# Tubes_1-3.net
KiCad netlist of a schematic drawn in Altium Designer
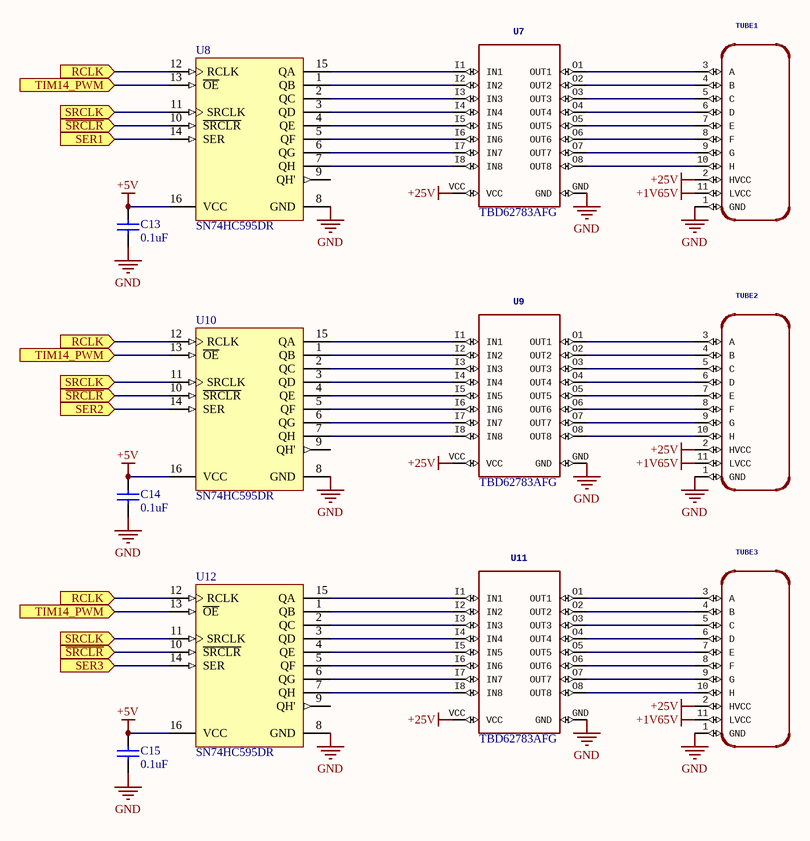
[diagram p0: Tubes 1-3.SchDoc]

(export (version "E")
  (design (tool "Eeschema 10.0.6"))
  (components
    (comp (ref "C13")
      (value "0.1uF")
      (footprint "CAPC1608X90X40ML10T20")
      (fields (field (name "TOLERANCE") "±10%") (field (name "MANUFACTURER") "Yageo"))
      (libsource (lib "Altium Content Vault") (part "CAP-NP-2"))
    )
    (comp (ref "C14")
      (value "0.1uF")
      (footprint "CAPC1608X90X40ML10T20")
      (fields (field (name "TOLERANCE") "±10%") (field (name "MANUFACTURER") "Yageo"))
      (libsource (lib "Altium Content Vault") (part "CAP-NP-2"))
    )
    (comp (ref "C15")
      (value "0.1uF")
      (footprint "CAPC1608X90X40ML10T20")
      (fields (field (name "TOLERANCE") "±10%") (field (name "MANUFACTURER") "Yageo"))
      (libsource (lib "Altium Content Vault") (part "CAP-NP-2"))
    )
    (comp (ref "TUBE1")
      (value "VFD-IV-11")
      (footprint "VFD-IV11")
      (libsource (lib "VFD-Clock") (part "VFD-IV-11"))
    )
    (comp (ref "TUBE2")
      (value "VFD-IV-11")
      (footprint "VFD-IV11")
      (libsource (lib "VFD-Clock") (part "VFD-IV-11"))
    )
    (comp (ref "TUBE3")
      (value "VFD-IV-11")
      (footprint "VFD-IV11")
      (libsource (lib "VFD-Clock") (part "VFD-IV-11"))
    )
    (comp (ref "U7")
      (value "TBD62783AFG")
      (footprint "TBD62783AFG")
      (description "TUBE1")
      (libsource (lib "TBD62783AFG") (part "TBD62783AFG"))
    )
    (comp (ref "U8")
      (value "SN74HC595DR")
      (footprint "D0016A_N")
      (description "8-Bit Shift Registers With 3-State Output Registers, D0016A, LARGE T&R")
      (fields
        (field (name "GENERIC PART NUMBER") "SN74HC595")
        (field (name "MANUFACTURER") "Texas Instruments")
      )
      (libsource (lib "VFD_Clock_lib") (part "CMP-0780-00037-3"))
    )
    (comp (ref "U9")
      (value "TBD62783AFG")
      (footprint "TBD62783AFG")
      (description "TUBE2")
      (libsource (lib "TBD62783AFG") (part "TBD62783AFG"))
    )
    (comp (ref "U10")
      (value "SN74HC595DR")
      (footprint "D0016A_N")
      (description "8-Bit Shift Registers With 3-State Output Registers, D0016A, LARGE T&R")
      (fields
        (field (name "GENERIC PART NUMBER") "SN74HC595")
        (field (name "MANUFACTURER") "Texas Instruments")
      )
      (libsource (lib "VFD_Clock_lib") (part "CMP-0780-00037-3"))
    )
    (comp (ref "U11")
      (value "TBD62783AFG")
      (footprint "TBD62783AFG")
      (description "TUBE3")
      (libsource (lib "TBD62783AFG") (part "TBD62783AFG"))
    )
    (comp (ref "U12")
      (value "SN74HC595DR")
      (footprint "D0016A_N")
      (description "8-Bit Shift Registers With 3-State Output Registers, D0016A, LARGE T&R")
      (fields
        (field (name "GENERIC PART NUMBER") "SN74HC595")
        (field (name "MANUFACTURER") "Texas Instruments")
      )
      (libsource (lib "VFD_Clock_lib") (part "CMP-0780-00037-3"))
    )
  )
  (nets
    (net (code "1") (name "+1V65V") (class "Default")
      (node (ref "TUBE1") (pin "11") (pinfunction "LVCC_11") (pintype "bidirectional"))
      (node (ref "TUBE2") (pin "11") (pinfunction "LVCC_11") (pintype "bidirectional"))
      (node (ref "TUBE3") (pin "11") (pinfunction "LVCC_11") (pintype "bidirectional"))
    )
    (net (code "2") (name "+5V") (class "Default")
      (node (ref "C13") (pin "2") (pinfunction "2_2") (pintype "passive"))
      (node (ref "C14") (pin "2") (pinfunction "2_2") (pintype "passive"))
      (node (ref "C15") (pin "2") (pinfunction "2_2") (pintype "passive"))
      (node (ref "U10") (pin "16") (pinfunction "VCC_16") (pintype "power_in"))
      (node (ref "U12") (pin "16") (pinfunction "VCC_16") (pintype "power_in"))
      (node (ref "U8") (pin "16") (pinfunction "VCC_16") (pintype "power_in"))
    )
    (net (code "3") (name "+25V") (class "Default")
      (node (ref "TUBE1") (pin "2") (pinfunction "HVCC_2") (pintype "bidirectional"))
      (node (ref "TUBE2") (pin "2") (pinfunction "HVCC_2") (pintype "bidirectional"))
      (node (ref "TUBE3") (pin "2") (pinfunction "HVCC_2") (pintype "bidirectional"))
      (node (ref "U11") (pin "VCC") (pinfunction "VCC_VCC") (pintype "bidirectional"))
      (node (ref "U7") (pin "VCC") (pinfunction "VCC_VCC") (pintype "bidirectional"))
      (node (ref "U9") (pin "VCC") (pinfunction "VCC_VCC") (pintype "bidirectional"))
    )
    (net (code "4") (name "/RCLK") (class "Default")
      (node (ref "U10") (pin "12") (pinfunction "RCLK_12") (pintype "input"))
      (node (ref "U12") (pin "12") (pinfunction "RCLK_12") (pintype "input"))
      (node (ref "U8") (pin "12") (pinfunction "RCLK_12") (pintype "input"))
    )
    (net (code "5") (name "/SER1") (class "Default")
      (node (ref "U8") (pin "14") (pinfunction "SER_14") (pintype "input"))
    )
    (net (code "6") (name "/SER2") (class "Default")
      (node (ref "U10") (pin "14") (pinfunction "SER_14") (pintype "input"))
    )
    (net (code "7") (name "/SER3") (class "Default")
      (node (ref "U12") (pin "14") (pinfunction "SER_14") (pintype "input"))
    )
    (net (code "8") (name "/SRCLK") (class "Default")
      (node (ref "U10") (pin "11") (pinfunction "SRCLK_11") (pintype "input"))
      (node (ref "U12") (pin "11") (pinfunction "SRCLK_11") (pintype "input"))
      (node (ref "U8") (pin "11") (pinfunction "SRCLK_11") (pintype "input"))
    )
    (net (code "9") (name "/SRCLR") (class "Default")
      (node (ref "U10") (pin "10") (pinfunction "~{SRCLR}_10") (pintype "input"))
      (node (ref "U12") (pin "10") (pinfunction "~{SRCLR}_10") (pintype "input"))
      (node (ref "U8") (pin "10") (pinfunction "~{SRCLR}_10") (pintype "input"))
    )
    (net (code "10") (name "/TIM14_PWM") (class "Default")
      (node (ref "U10") (pin "13") (pinfunction "~{OE}_13") (pintype "input"))
      (node (ref "U12") (pin "13") (pinfunction "~{OE}_13") (pintype "input"))
      (node (ref "U8") (pin "13") (pinfunction "~{OE}_13") (pintype "input"))
    )
    (net (code "11") (name "GND") (class "Default")
      (node (ref "C13") (pin "1") (pinfunction "1_1") (pintype "passive"))
      (node (ref "C14") (pin "1") (pinfunction "1_1") (pintype "passive"))
      (node (ref "C15") (pin "1") (pinfunction "1_1") (pintype "passive"))
      (node (ref "TUBE1") (pin "1") (pinfunction "GND_1") (pintype "bidirectional"))
      (node (ref "TUBE2") (pin "1") (pinfunction "GND_1") (pintype "bidirectional"))
      (node (ref "TUBE3") (pin "1") (pinfunction "GND_1") (pintype "bidirectional"))
      (node (ref "U10") (pin "8") (pinfunction "GND_8") (pintype "power_in"))
      (node (ref "U11") (pin "GND") (pinfunction "GND_GND") (pintype "bidirectional"))
      (node (ref "U12") (pin "8") (pinfunction "GND_8") (pintype "power_in"))
      (node (ref "U7") (pin "GND") (pinfunction "GND_GND") (pintype "bidirectional"))
      (node (ref "U8") (pin "8") (pinfunction "GND_8") (pintype "power_in"))
      (node (ref "U9") (pin "GND") (pinfunction "GND_GND") (pintype "bidirectional"))
    )
    (net (code "12") (name "Net-(TUBE1-A)") (class "Default")
      (node (ref "TUBE1") (pin "3") (pinfunction "A_3") (pintype "bidirectional"))
      (node (ref "U7") (pin "O1") (pinfunction "OUT1_O1") (pintype "bidirectional"))
    )
    (net (code "13") (name "Net-(TUBE1-B)") (class "Default")
      (node (ref "TUBE1") (pin "4") (pinfunction "B_4") (pintype "bidirectional"))
      (node (ref "U7") (pin "O2") (pinfunction "OUT2_O2") (pintype "bidirectional"))
    )
    (net (code "14") (name "Net-(TUBE1-C)") (class "Default")
      (node (ref "TUBE1") (pin "5") (pinfunction "C_5") (pintype "bidirectional"))
      (node (ref "U7") (pin "O3") (pinfunction "OUT3_O3") (pintype "bidirectional"))
    )
    (net (code "15") (name "Net-(TUBE1-D)") (class "Default")
      (node (ref "TUBE1") (pin "6") (pinfunction "D_6") (pintype "bidirectional"))
      (node (ref "U7") (pin "O4") (pinfunction "OUT4_O4") (pintype "bidirectional"))
    )
    (net (code "16") (name "Net-(TUBE1-E)") (class "Default")
      (node (ref "TUBE1") (pin "7") (pinfunction "E_7") (pintype "bidirectional"))
      (node (ref "U7") (pin "O5") (pinfunction "OUT5_O5") (pintype "bidirectional"))
    )
    (net (code "17") (name "Net-(TUBE1-F)") (class "Default")
      (node (ref "TUBE1") (pin "8") (pinfunction "F_8") (pintype "bidirectional"))
      (node (ref "U7") (pin "O6") (pinfunction "OUT6_O6") (pintype "bidirectional"))
    )
    (net (code "18") (name "Net-(TUBE1-G)") (class "Default")
      (node (ref "TUBE1") (pin "9") (pinfunction "G_9") (pintype "bidirectional"))
      (node (ref "U7") (pin "O7") (pinfunction "OUT7_O7") (pintype "bidirectional"))
    )
    (net (code "19") (name "Net-(TUBE1-H)") (class "Default")
      (node (ref "TUBE1") (pin "10") (pinfunction "H_10") (pintype "bidirectional"))
      (node (ref "U7") (pin "O8") (pinfunction "OUT8_O8") (pintype "bidirectional"))
    )
    (net (code "20") (name "Net-(TUBE2-A)") (class "Default")
      (node (ref "TUBE2") (pin "3") (pinfunction "A_3") (pintype "bidirectional"))
      (node (ref "U9") (pin "O1") (pinfunction "OUT1_O1") (pintype "bidirectional"))
    )
    (net (code "21") (name "Net-(TUBE2-B)") (class "Default")
      (node (ref "TUBE2") (pin "4") (pinfunction "B_4") (pintype "bidirectional"))
      (node (ref "U9") (pin "O2") (pinfunction "OUT2_O2") (pintype "bidirectional"))
    )
    (net (code "22") (name "Net-(TUBE2-C)") (class "Default")
      (node (ref "TUBE2") (pin "5") (pinfunction "C_5") (pintype "bidirectional"))
      (node (ref "U9") (pin "O3") (pinfunction "OUT3_O3") (pintype "bidirectional"))
    )
    (net (code "23") (name "Net-(TUBE2-D)") (class "Default")
      (node (ref "TUBE2") (pin "6") (pinfunction "D_6") (pintype "bidirectional"))
      (node (ref "U9") (pin "O4") (pinfunction "OUT4_O4") (pintype "bidirectional"))
    )
    (net (code "24") (name "Net-(TUBE2-E)") (class "Default")
      (node (ref "TUBE2") (pin "7") (pinfunction "E_7") (pintype "bidirectional"))
      (node (ref "U9") (pin "O5") (pinfunction "OUT5_O5") (pintype "bidirectional"))
    )
    (net (code "25") (name "Net-(TUBE2-F)") (class "Default")
      (node (ref "TUBE2") (pin "8") (pinfunction "F_8") (pintype "bidirectional"))
      (node (ref "U9") (pin "O6") (pinfunction "OUT6_O6") (pintype "bidirectional"))
    )
    (net (code "26") (name "Net-(TUBE2-G)") (class "Default")
      (node (ref "TUBE2") (pin "9") (pinfunction "G_9") (pintype "bidirectional"))
      (node (ref "U9") (pin "O7") (pinfunction "OUT7_O7") (pintype "bidirectional"))
    )
    (net (code "27") (name "Net-(TUBE2-H)") (class "Default")
      (node (ref "TUBE2") (pin "10") (pinfunction "H_10") (pintype "bidirectional"))
      (node (ref "U9") (pin "O8") (pinfunction "OUT8_O8") (pintype "bidirectional"))
    )
    (net (code "28") (name "Net-(TUBE3-A)") (class "Default")
      (node (ref "TUBE3") (pin "3") (pinfunction "A_3") (pintype "bidirectional"))
      (node (ref "U11") (pin "O1") (pinfunction "OUT1_O1") (pintype "bidirectional"))
    )
    (net (code "29") (name "Net-(TUBE3-B)") (class "Default")
      (node (ref "TUBE3") (pin "4") (pinfunction "B_4") (pintype "bidirectional"))
      (node (ref "U11") (pin "O2") (pinfunction "OUT2_O2") (pintype "bidirectional"))
    )
    (net (code "30") (name "Net-(TUBE3-C)") (class "Default")
      (node (ref "TUBE3") (pin "5") (pinfunction "C_5") (pintype "bidirectional"))
      (node (ref "U11") (pin "O3") (pinfunction "OUT3_O3") (pintype "bidirectional"))
    )
    (net (code "31") (name "Net-(TUBE3-D)") (class "Default")
      (node (ref "TUBE3") (pin "6") (pinfunction "D_6") (pintype "bidirectional"))
      (node (ref "U11") (pin "O4") (pinfunction "OUT4_O4") (pintype "bidirectional"))
    )
    (net (code "32") (name "Net-(TUBE3-E)") (class "Default")
      (node (ref "TUBE3") (pin "7") (pinfunction "E_7") (pintype "bidirectional"))
      (node (ref "U11") (pin "O5") (pinfunction "OUT5_O5") (pintype "bidirectional"))
    )
    (net (code "33") (name "Net-(TUBE3-F)") (class "Default")
      (node (ref "TUBE3") (pin "8") (pinfunction "F_8") (pintype "bidirectional"))
      (node (ref "U11") (pin "O6") (pinfunction "OUT6_O6") (pintype "bidirectional"))
    )
    (net (code "34") (name "Net-(TUBE3-G)") (class "Default")
      (node (ref "TUBE3") (pin "9") (pinfunction "G_9") (pintype "bidirectional"))
      (node (ref "U11") (pin "O7") (pinfunction "OUT7_O7") (pintype "bidirectional"))
    )
    (net (code "35") (name "Net-(TUBE3-H)") (class "Default")
      (node (ref "TUBE3") (pin "10") (pinfunction "H_10") (pintype "bidirectional"))
      (node (ref "U11") (pin "O8") (pinfunction "OUT8_O8") (pintype "bidirectional"))
    )
    (net (code "36") (name "Net-(U7-IN1)") (class "Default")
      (node (ref "U7") (pin "I1") (pinfunction "IN1_I1") (pintype "bidirectional"))
      (node (ref "U8") (pin "15") (pinfunction "QA_15") (pintype "tri_state"))
    )
    (net (code "37") (name "Net-(U7-IN2)") (class "Default")
      (node (ref "U7") (pin "I2") (pinfunction "IN2_I2") (pintype "bidirectional"))
      (node (ref "U8") (pin "1") (pinfunction "QB_1") (pintype "tri_state"))
    )
    (net (code "38") (name "Net-(U7-IN3)") (class "Default")
      (node (ref "U7") (pin "I3") (pinfunction "IN3_I3") (pintype "bidirectional"))
      (node (ref "U8") (pin "2") (pinfunction "QC_2") (pintype "tri_state"))
    )
    (net (code "39") (name "Net-(U7-IN4)") (class "Default")
      (node (ref "U7") (pin "I4") (pinfunction "IN4_I4") (pintype "bidirectional"))
      (node (ref "U8") (pin "3") (pinfunction "QD_3") (pintype "tri_state"))
    )
    (net (code "40") (name "Net-(U7-IN5)") (class "Default")
      (node (ref "U7") (pin "I5") (pinfunction "IN5_I5") (pintype "bidirectional"))
      (node (ref "U8") (pin "4") (pinfunction "QE_4") (pintype "tri_state"))
    )
    (net (code "41") (name "Net-(U7-IN6)") (class "Default")
      (node (ref "U7") (pin "I6") (pinfunction "IN6_I6") (pintype "bidirectional"))
      (node (ref "U8") (pin "5") (pinfunction "QF_5") (pintype "tri_state"))
    )
    (net (code "42") (name "Net-(U7-IN7)") (class "Default")
      (node (ref "U7") (pin "I7") (pinfunction "IN7_I7") (pintype "bidirectional"))
      (node (ref "U8") (pin "6") (pinfunction "QG_6") (pintype "tri_state"))
    )
    (net (code "43") (name "Net-(U7-IN8)") (class "Default")
      (node (ref "U7") (pin "I8") (pinfunction "IN8_I8") (pintype "bidirectional"))
      (node (ref "U8") (pin "7") (pinfunction "QH_7") (pintype "tri_state"))
    )
    (net (code "44") (name "Net-(U10-QA)") (class "Default")
      (node (ref "U10") (pin "15") (pinfunction "QA_15") (pintype "tri_state"))
      (node (ref "U9") (pin "I1") (pinfunction "IN1_I1") (pintype "bidirectional"))
    )
    (net (code "45") (name "Net-(U10-QB)") (class "Default")
      (node (ref "U10") (pin "1") (pinfunction "QB_1") (pintype "tri_state"))
      (node (ref "U9") (pin "I2") (pinfunction "IN2_I2") (pintype "bidirectional"))
    )
    (net (code "46") (name "Net-(U10-QC)") (class "Default")
      (node (ref "U10") (pin "2") (pinfunction "QC_2") (pintype "tri_state"))
      (node (ref "U9") (pin "I3") (pinfunction "IN3_I3") (pintype "bidirectional"))
    )
    (net (code "47") (name "Net-(U10-QD)") (class "Default")
      (node (ref "U10") (pin "3") (pinfunction "QD_3") (pintype "tri_state"))
      (node (ref "U9") (pin "I4") (pinfunction "IN4_I4") (pintype "bidirectional"))
    )
    (net (code "48") (name "Net-(U10-QE)") (class "Default")
      (node (ref "U10") (pin "4") (pinfunction "QE_4") (pintype "tri_state"))
      (node (ref "U9") (pin "I5") (pinfunction "IN5_I5") (pintype "bidirectional"))
    )
    (net (code "49") (name "Net-(U10-QF)") (class "Default")
      (node (ref "U10") (pin "5") (pinfunction "QF_5") (pintype "tri_state"))
      (node (ref "U9") (pin "I6") (pinfunction "IN6_I6") (pintype "bidirectional"))
    )
    (net (code "50") (name "Net-(U10-QG)") (class "Default")
      (node (ref "U10") (pin "6") (pinfunction "QG_6") (pintype "tri_state"))
      (node (ref "U9") (pin "I7") (pinfunction "IN7_I7") (pintype "bidirectional"))
    )
    (net (code "51") (name "Net-(U10-QH)") (class "Default")
      (node (ref "U10") (pin "7") (pinfunction "QH_7") (pintype "tri_state"))
      (node (ref "U9") (pin "I8") (pinfunction "IN8_I8") (pintype "bidirectional"))
    )
    (net (code "52") (name "Net-(U11-IN1)") (class "Default")
      (node (ref "U11") (pin "I1") (pinfunction "IN1_I1") (pintype "bidirectional"))
      (node (ref "U12") (pin "15") (pinfunction "QA_15") (pintype "tri_state"))
    )
    (net (code "53") (name "Net-(U11-IN2)") (class "Default")
      (node (ref "U11") (pin "I2") (pinfunction "IN2_I2") (pintype "bidirectional"))
      (node (ref "U12") (pin "1") (pinfunction "QB_1") (pintype "tri_state"))
    )
    (net (code "54") (name "Net-(U11-IN3)") (class "Default")
      (node (ref "U11") (pin "I3") (pinfunction "IN3_I3") (pintype "bidirectional"))
      (node (ref "U12") (pin "2") (pinfunction "QC_2") (pintype "tri_state"))
    )
    (net (code "55") (name "Net-(U11-IN4)") (class "Default")
      (node (ref "U11") (pin "I4") (pinfunction "IN4_I4") (pintype "bidirectional"))
      (node (ref "U12") (pin "3") (pinfunction "QD_3") (pintype "tri_state"))
    )
    (net (code "56") (name "Net-(U11-IN5)") (class "Default")
      (node (ref "U11") (pin "I5") (pinfunction "IN5_I5") (pintype "bidirectional"))
      (node (ref "U12") (pin "4") (pinfunction "QE_4") (pintype "tri_state"))
    )
    (net (code "57") (name "Net-(U11-IN6)") (class "Default")
      (node (ref "U11") (pin "I6") (pinfunction "IN6_I6") (pintype "bidirectional"))
      (node (ref "U12") (pin "5") (pinfunction "QF_5") (pintype "tri_state"))
    )
    (net (code "58") (name "Net-(U11-IN7)") (class "Default")
      (node (ref "U11") (pin "I7") (pinfunction "IN7_I7") (pintype "bidirectional"))
      (node (ref "U12") (pin "6") (pinfunction "QG_6") (pintype "tri_state"))
    )
    (net (code "59") (name "Net-(U11-IN8)") (class "Default")
      (node (ref "U11") (pin "I8") (pinfunction "IN8_I8") (pintype "bidirectional"))
      (node (ref "U12") (pin "7") (pinfunction "QH_7") (pintype "tri_state"))
    )
    (net (code "60") (name "unconnected-(U8-QH'-Pad9)") (class "Default")
      (node (ref "U8") (pin "9") (pinfunction "QH'_9") (pintype "output"))
    )
    (net (code "61") (name "unconnected-(U10-QH'-Pad9)") (class "Default")
      (node (ref "U10") (pin "9") (pinfunction "QH'_9") (pintype "output"))
    )
    (net (code "62") (name "unconnected-(U12-QH'-Pad9)") (class "Default")
      (node (ref "U12") (pin "9") (pinfunction "QH'_9") (pintype "output"))
    )
  )
)
